# main.net
KiCad netlist of a schematic drawn in Altium Designer
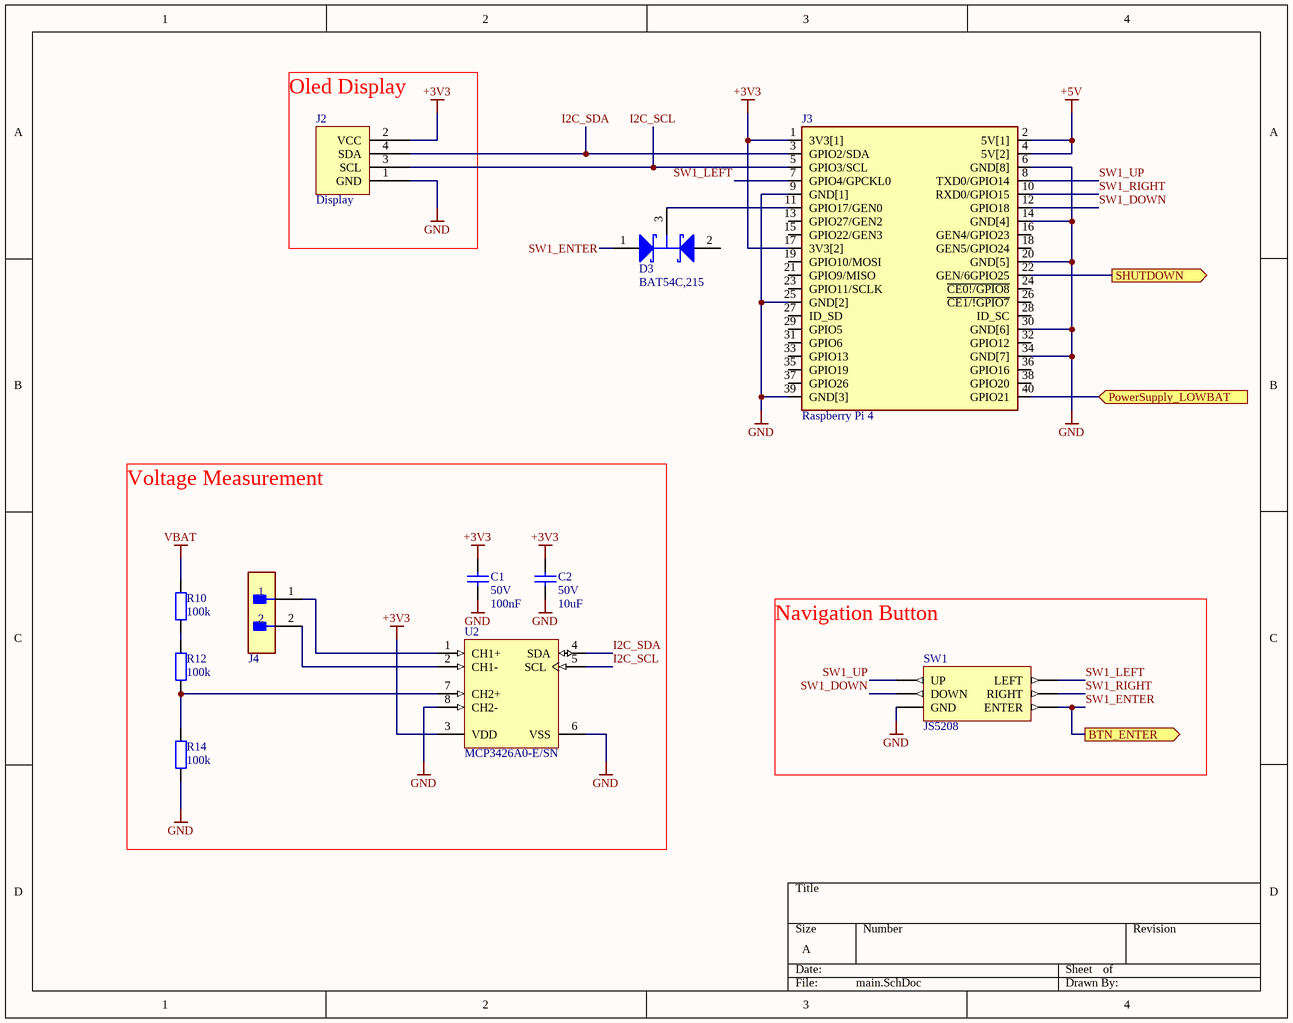
[diagram p0: main.SchDoc]

(export (version "E")
  (design (tool "Eeschema 10.0.6"))
  (components
    (comp (ref "C1")
      (value "100nF")
      (footprint "CAPC2013X88X50NL20T25")
      (description "Ceramic Capacitor X7R")
      (fields (field (name "VOLTAGE RATING") "50V") (field (name "Comment") "Cap_0805"))
      (libsource (lib "Biral_Generic") (part "Cap_0805"))
    )
    (comp (ref "C2")
      (value "10uF")
      (footprint "CAPC2013X88X50NL20T25")
      (description "Ceramic Capacitor X7R")
      (fields (field (name "VOLTAGE RATING") "50V") (field (name "Comment") "Cap_0805"))
      (libsource (lib "Biral_Generic") (part "Cap_0805"))
    )
    (comp (ref "D3")
      (value "BAT54C,215")
      (footprint "SOT23")
      (description "Schottky Barrier Diode, 30 V, 3-Pin SOT23, RoHS, Tape and Reel")
      (fields (field (name "MANUFACTURER") "NXP Semiconductors"))
      (libsource (lib "Schlib") (part "DIODE_BAT54C"))
    )
    (comp (ref "J2")
      (value "Display")
      (footprint "OLED_DISPLAY")
      (fields (field (name "MANUFACTURER") "Samtec") (field (name "PARTNUMBER") "MMS-104-01-T-SV"))
      (libsource (lib "Schlib") (part "Oled Display"))
    )
    (comp (ref "J3")
      (value "Raspberry Pi 4")
      (footprint "RASPBERRY_PI_4")
      (description "Raspberry Pi 4 with Headers_")
      (fields (field (name "MP") "ADA3708") (field (name "MF") "Raspberry Pi"))
      (libsource (lib "Schlib") (part "RASPBERRY_PI4"))
    )
    (comp (ref "J4")
      (value "ADC_header")
      (footprint "ADC_HEADER")
      (libsource (lib "Schlib") (part "ADC_header"))
    )
    (comp (ref "R10")
      (value "100k")
      (footprint "RESC2013X50X30NL20T20")
      (description "Resistor")
      (fields (field (name "TOLERANCE") "1%") (field (name "Comment") "Res_0805"))
      (libsource (lib "Biral_Generic") (part "Res_0805"))
    )
    (comp (ref "R12")
      (value "100k")
      (footprint "RESC2013X50X30NL20T20")
      (description "Resistor")
      (fields (field (name "TOLERANCE") "1%") (field (name "Comment") "Res_0805"))
      (libsource (lib "Biral_Generic") (part "Res_0805"))
    )
    (comp (ref "R14")
      (value "100k")
      (footprint "RESC2013X50X30NL20T20")
      (description "Resistor")
      (fields (field (name "TOLERANCE") "1%") (field (name "Comment") "Res_0805"))
      (libsource (lib "Biral_Generic") (part "Res_0805"))
    )
    (comp (ref "SW1")
      (value "JS5208")
      (footprint "JS5208_PKG")
      (description "E-SWITCH - JS5208 - SWITCH, NAVIGATION, 5 POSITION, 20mA, SMD")
      (fields (field (name "MANUFACTURER") "E-Switch"))
      (libsource (lib "Schlib") (part "NAV_BUTTON"))
    )
    (comp (ref "U2")
      (value "MCP3426A0-E/SN")
      (footprint "SOIC-SN8_L")
      (libsource (lib "Altium Content Vault") (part "CON-ADC-MCP3426-8"))
    )
  )
  (nets
    (net (code "1") (name "+3V3") (class "Default")
      (node (ref "C1") (pin "2") (pinfunction "2_2") (pintype "passive"))
      (node (ref "C2") (pin "2") (pinfunction "2_2") (pintype "passive"))
      (node (ref "J2") (pin "2") (pinfunction "VCC_2") (pintype "passive"))
      (node (ref "J3") (pin "1") (pinfunction "3V3[1]_1") (pintype "power_in"))
      (node (ref "J3") (pin "17") (pinfunction "3V3[2]_17") (pintype "power_in"))
      (node (ref "U2") (pin "3") (pinfunction "VDD_3") (pintype "power_in"))
    )
    (net (code "2") (name "+5V") (class "Default")
      (node (ref "J3") (pin "2") (pinfunction "5V[1]_2") (pintype "power_in"))
      (node (ref "J3") (pin "4") (pinfunction "5V[2]_4") (pintype "power_in"))
    )
    (net (code "3") (name "/I2C_SCL") (class "Default")
      (node (ref "J2") (pin "3") (pinfunction "SCL_3") (pintype "passive"))
      (node (ref "J3") (pin "5") (pinfunction "GPIO3/SCL_5") (pintype "bidirectional"))
      (node (ref "U2") (pin "5") (pinfunction "SCL_5") (pintype "input"))
    )
    (net (code "4") (name "/I2C_SDA") (class "Default")
      (node (ref "J2") (pin "4") (pinfunction "SDA_4") (pintype "passive"))
      (node (ref "J3") (pin "3") (pinfunction "GPIO2/SDA_3") (pintype "bidirectional"))
      (node (ref "U2") (pin "4") (pinfunction "SDA_4") (pintype "bidirectional"))
    )
    (net (code "5") (name "/PowerSupply_LOWBAT") (class "Default")
      (node (ref "J3") (pin "40") (pinfunction "GPIO21_40") (pintype "bidirectional"))
    )
    (net (code "6") (name "/SHUTDOWN") (class "Default")
      (node (ref "J3") (pin "22") (pinfunction "GEN/6GPIO25_22") (pintype "bidirectional"))
    )
    (net (code "7") (name "/SW1_DOWN") (class "Default")
      (node (ref "J3") (pin "12") (pinfunction "GPIO18_12") (pintype "bidirectional"))
      (node (ref "SW1") (pin "C-D") (pinfunction "DOWN_C-D") (pintype "output"))
    )
    (net (code "8") (name "/SW1_ENTER") (class "Default")
      (node (ref "D3") (pin "1") (pinfunction "A_1") (pintype "passive"))
      (node (ref "SW1") (pin "E-BTN") (pinfunction "ENTER_E-BTN") (pintype "output"))
    )
    (net (code "9") (name "/SW1_LEFT") (class "Default")
      (node (ref "J3") (pin "7") (pinfunction "GPIO4/GPCKL0_7") (pintype "bidirectional"))
      (node (ref "SW1") (pin "B-L") (pinfunction "LEFT_B-L") (pintype "output"))
    )
    (net (code "10") (name "/SW1_RIGHT") (class "Default")
      (node (ref "J3") (pin "10") (pinfunction "RXD0/GPIO15_10") (pintype "bidirectional"))
      (node (ref "SW1") (pin "D-R") (pinfunction "RIGHT_D-R") (pintype "output"))
    )
    (net (code "11") (name "/SW1_UP") (class "Default")
      (node (ref "J3") (pin "8") (pinfunction "TXD0/GPIO14_8") (pintype "bidirectional"))
      (node (ref "SW1") (pin "A-U") (pinfunction "UP_A-U") (pintype "output"))
    )
    (net (code "12") (name "GND") (class "Default")
      (node (ref "C1") (pin "1") (pinfunction "1_1") (pintype "passive"))
      (node (ref "C2") (pin "1") (pinfunction "1_1") (pintype "passive"))
      (node (ref "J2") (pin "1") (pinfunction "GND_1") (pintype "passive"))
      (node (ref "J3") (pin "14") (pinfunction "GND[4]_14") (pintype "power_in"))
      (node (ref "J3") (pin "20") (pinfunction "GND[5]_20") (pintype "power_in"))
      (node (ref "J3") (pin "25") (pinfunction "GND[2]_25") (pintype "power_in"))
      (node (ref "J3") (pin "30") (pinfunction "GND[6]_30") (pintype "power_in"))
      (node (ref "J3") (pin "34") (pinfunction "GND[7]_34") (pintype "power_in"))
      (node (ref "J3") (pin "39") (pinfunction "GND[3]_39") (pintype "power_in"))
      (node (ref "J3") (pin "6") (pinfunction "GND[8]_6") (pintype "power_in"))
      (node (ref "J3") (pin "9") (pinfunction "GND[1]_9") (pintype "power_in"))
      (node (ref "R14") (pin "1") (pinfunction "1_1") (pintype "passive"))
      (node (ref "SW1") (pin "COM") (pinfunction "GND_COM") (pintype "power_in"))
      (node (ref "U2") (pin "6") (pinfunction "VSS_6") (pintype "power_in"))
      (node (ref "U2") (pin "8") (pinfunction "CH2-_8") (pintype "input"))
    )
    (net (code "13") (name "Net-(D3-K)") (class "Default")
      (node (ref "D3") (pin "3") (pinfunction "K_3") (pintype "passive"))
      (node (ref "J3") (pin "11") (pinfunction "GPIO17/GEN0_11") (pintype "bidirectional"))
    )
    (net (code "14") (name "Net-(R10-Pad1)") (class "Default")
      (node (ref "R10") (pin "1") (pinfunction "1_1") (pintype "passive"))
      (node (ref "R12") (pin "2") (pinfunction "2_2") (pintype "passive"))
    )
    (net (code "15") (name "Net-(U2-CH1+)") (class "Default")
      (node (ref "J4") (pin "1") (pinfunction "1_1") (pintype "passive"))
      (node (ref "U2") (pin "1") (pinfunction "CH1+_1") (pintype "input"))
    )
    (net (code "16") (name "Net-(U2-CH1-)") (class "Default")
      (node (ref "J4") (pin "2") (pinfunction "2_2") (pintype "passive"))
      (node (ref "U2") (pin "2") (pinfunction "CH1-_2") (pintype "input"))
    )
    (net (code "17") (name "Net-(U2-CH2+)") (class "Default")
      (node (ref "R12") (pin "1") (pinfunction "1_1") (pintype "passive"))
      (node (ref "R14") (pin "2") (pinfunction "2_2") (pintype "passive"))
      (node (ref "U2") (pin "7") (pinfunction "CH2+_7") (pintype "input"))
    )
    (net (code "18") (name "VBAT") (class "Default")
      (node (ref "R10") (pin "2") (pinfunction "2_2") (pintype "passive"))
    )
    (net (code "19") (name "unconnected-(D3-A-Pad2)") (class "Default")
      (node (ref "D3") (pin "2") (pinfunction "A_2") (pintype "passive"))
    )
    (net (code "20") (name "unconnected-(J3-GEN4{slash}GPIO23-Pad16)") (class "Default")
      (node (ref "J3") (pin "16") (pinfunction "GEN4/GPIO23_16") (pintype "bidirectional"))
    )
    (net (code "21") (name "unconnected-(J3-GEN5{slash}GPIO24-Pad18)") (class "Default")
      (node (ref "J3") (pin "18") (pinfunction "GEN5/GPIO24_18") (pintype "bidirectional"))
    )
    (net (code "22") (name "unconnected-(J3-GPIO5-Pad29)") (class "Default")
      (node (ref "J3") (pin "29") (pinfunction "GPIO5_29") (pintype "bidirectional"))
    )
    (net (code "23") (name "unconnected-(J3-GPIO6-Pad31)") (class "Default")
      (node (ref "J3") (pin "31") (pinfunction "GPIO6_31") (pintype "bidirectional"))
    )
    (net (code "24") (name "unconnected-(J3-GPIO9{slash}MISO-Pad21)") (class "Default")
      (node (ref "J3") (pin "21") (pinfunction "GPIO9/MISO_21") (pintype "bidirectional"))
    )
    (net (code "25") (name "unconnected-(J3-GPIO10{slash}MOSI-Pad19)") (class "Default")
      (node (ref "J3") (pin "19") (pinfunction "GPIO10/MOSI_19") (pintype "bidirectional"))
    )
    (net (code "26") (name "unconnected-(J3-GPIO11{slash}SCLK-Pad23)") (class "Default")
      (node (ref "J3") (pin "23") (pinfunction "GPIO11/SCLK_23") (pintype "bidirectional"))
    )
    (net (code "27") (name "unconnected-(J3-GPIO12-Pad32)") (class "Default")
      (node (ref "J3") (pin "32") (pinfunction "GPIO12_32") (pintype "bidirectional"))
    )
    (net (code "28") (name "unconnected-(J3-GPIO13-Pad33)") (class "Default")
      (node (ref "J3") (pin "33") (pinfunction "GPIO13_33") (pintype "bidirectional"))
    )
    (net (code "29") (name "unconnected-(J3-GPIO16-Pad36)") (class "Default")
      (node (ref "J3") (pin "36") (pinfunction "GPIO16_36") (pintype "bidirectional"))
    )
    (net (code "30") (name "unconnected-(J3-GPIO19-Pad35)") (class "Default")
      (node (ref "J3") (pin "35") (pinfunction "GPIO19_35") (pintype "bidirectional"))
    )
    (net (code "31") (name "unconnected-(J3-GPIO20-Pad38)") (class "Default")
      (node (ref "J3") (pin "38") (pinfunction "GPIO20_38") (pintype "bidirectional"))
    )
    (net (code "32") (name "unconnected-(J3-GPIO22{slash}GEN3-Pad15)") (class "Default")
      (node (ref "J3") (pin "15") (pinfunction "GPIO22/GEN3_15") (pintype "bidirectional"))
    )
    (net (code "33") (name "unconnected-(J3-GPIO26-Pad37)") (class "Default")
      (node (ref "J3") (pin "37") (pinfunction "GPIO26_37") (pintype "bidirectional"))
    )
    (net (code "34") (name "unconnected-(J3-GPIO27{slash}GEN2-Pad13)") (class "Default")
      (node (ref "J3") (pin "13") (pinfunction "GPIO27/GEN2_13") (pintype "bidirectional"))
    )
    (net (code "35") (name "unconnected-(J3-ID_SC-Pad28)") (class "Default")
      (node (ref "J3") (pin "28") (pinfunction "ID_SC_28") (pintype "bidirectional"))
    )
    (net (code "36") (name "unconnected-(J3-ID_SD-Pad27)") (class "Default")
      (node (ref "J3") (pin "27") (pinfunction "ID_SD_27") (pintype "bidirectional"))
    )
    (net (code "37") (name "unconnected-(J3-~{CE0!{slash}GPIO8}-Pad24)") (class "Default")
      (node (ref "J3") (pin "24") (pinfunction "~{CE0!/GPIO8}_24") (pintype "bidirectional"))
    )
    (net (code "38") (name "unconnected-(J3-~{CE1{slash}!GPIO7}-Pad26)") (class "Default")
      (node (ref "J3") (pin "26") (pinfunction "~{CE1/!GPIO7}_26") (pintype "bidirectional"))
    )
  )
)
